# DebuggerConnectors.net
KiCad netlist of a schematic drawn in Altium Designer
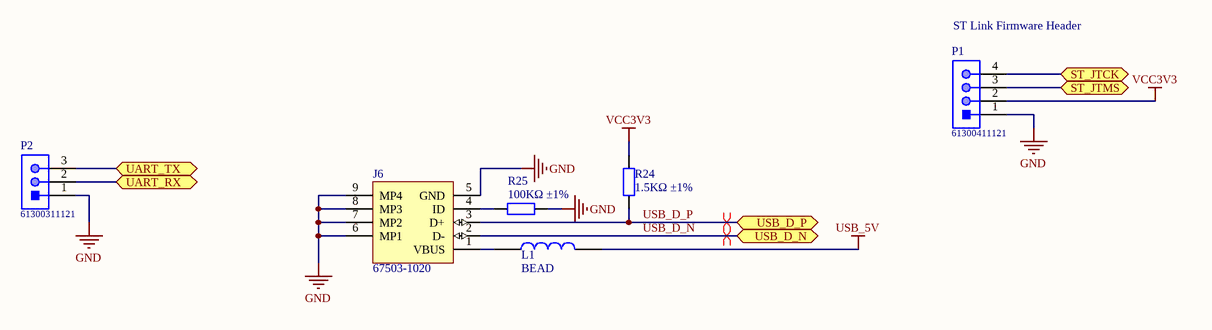
[diagram p0: DebuggerConnectors.SchDoc]

(export (version "E")
  (design (tool "Eeschema 10.0.6"))
  (components
    (comp (ref "J6")
      (value "67503-1020")
      (footprint "MOLX-67503-1020_V")
      (description "USB, MINI, SMD, RA KME04-USBMU03A01")
      (fields (field (name "MANUFACTURER") "Molex"))
      (libsource (lib "Altium Content Vault") (part "MOLX-67503-1020"))
    )
    (comp (ref "L1")
      (value "BEAD")
      (footprint "0603_L")
      (description "Ferrite Bead")
      (libsource (lib "FBEAD") (part "0603 100R@100Mhz 1A"))
    )
    (comp (ref "P1")
      (value "61300411121")
      (footprint "61300411121")
      (description "THT Vertical Pin Header WR-PHD, Pitch 2.54 mm, Single Row, 4 pins")
      (fields (field (name "MANUFACTURER") "Wurth Elektronik") (field (name "PUBLISHER") "WurthElektronik"))
      (libsource (lib "Altium Content Vault") (part "WE-CN-1P-M-R4"))
    )
    (comp (ref "P2")
      (value "61300311121")
      (footprint "61300311121")
      (description "THT Vertical Pin Header WR-PHD, Pitch 2.54 mm, Single Row, 3 pins")
      (fields (field (name "MANUFACTURER") "Wurth Elektronik") (field (name "PUBLISHER") "WurthElektronik"))
      (libsource (lib "Altium Content Vault") (part "WE-CN-1P-M-R3"))
    )
    (comp (ref "R24")
      (value "1.5KΩ ±1%")
      (footprint "0402_R")
      (description "Chip resistor")
      (fields (field (name "MANUFACTURER") "Uniroyal Elec") (field (name "PARTNUMBER") "0402WGF1501TCE"))
      (libsource (lib "Miscellaneous Devices LC") (part "0402 1.5K (1501) 1%"))
    )
    (comp (ref "R25")
      (value "100KΩ ±1%")
      (footprint "0402_R")
      (description "Chip resistor")
      (fields (field (name "MANUFACTURER") "Uniroyal Elec") (field (name "PARTNUMBER") "0402WGF1003TCE"))
      (libsource (lib "Miscellaneous Devices LC") (part "0402 100K (1003) 1%"))
    )
  )
  (nets
    (net (code "1") (name "/ST_JTCK") (class "Default")
      (node (ref "P1") (pin "4") (pinfunction "4_4") (pintype "passive"))
    )
    (net (code "2") (name "/ST_JTMS") (class "Default")
      (node (ref "P1") (pin "3") (pinfunction "3_3") (pintype "passive"))
    )
    (net (code "3") (name "/UART_RX") (class "Default")
      (node (ref "P2") (pin "2") (pinfunction "2_2") (pintype "passive"))
    )
    (net (code "4") (name "/UART_TX") (class "Default")
      (node (ref "P2") (pin "3") (pinfunction "3_3") (pintype "passive"))
    )
    (net (code "5") (name "/USB_D_N") (class "Default")
      (node (ref "J6") (pin "2") (pinfunction "D-_2") (pintype "bidirectional"))
    )
    (net (code "6") (name "/USB_D_P") (class "Default")
      (node (ref "J6") (pin "3") (pinfunction "D+_3") (pintype "bidirectional"))
      (node (ref "R24") (pin "1") (pinfunction "1_1") (pintype "passive"))
    )
    (net (code "7") (name "GND") (class "Default")
      (node (ref "J6") (pin "5") (pinfunction "GND_5") (pintype "power_in"))
      (node (ref "J6") (pin "6") (pinfunction "MP1_6") (pintype "passive"))
      (node (ref "J6") (pin "7") (pinfunction "MP2_7") (pintype "passive"))
      (node (ref "J6") (pin "8") (pinfunction "MP3_8") (pintype "passive"))
      (node (ref "J6") (pin "9") (pinfunction "MP4_9") (pintype "passive"))
      (node (ref "P1") (pin "1") (pinfunction "1_1") (pintype "passive"))
      (node (ref "P2") (pin "1") (pinfunction "1_1") (pintype "passive"))
      (node (ref "R25") (pin "2") (pinfunction "2_2") (pintype "passive"))
    )
    (net (code "8") (name "Net-(J6-ID)") (class "Default")
      (node (ref "J6") (pin "4") (pinfunction "ID_4") (pintype "passive"))
      (node (ref "R25") (pin "1") (pinfunction "1_1") (pintype "passive"))
    )
    (net (code "9") (name "Net-(J6-VBUS)") (class "Default")
      (node (ref "J6") (pin "1") (pinfunction "VBUS_1") (pintype "power_in"))
      (node (ref "L1") (pin "1") (pinfunction "1_1") (pintype "passive"))
    )
    (net (code "10") (name "USB_5V") (class "Default")
      (node (ref "L1") (pin "2") (pinfunction "2_2") (pintype "passive"))
    )
    (net (code "11") (name "VCC3V3") (class "Default")
      (node (ref "P1") (pin "2") (pinfunction "2_2") (pintype "passive"))
      (node (ref "R24") (pin "2") (pinfunction "2_2") (pintype "passive"))
    )
  )
)
